# button_circle.net
KiCad netlist of a schematic drawn in EAGLE
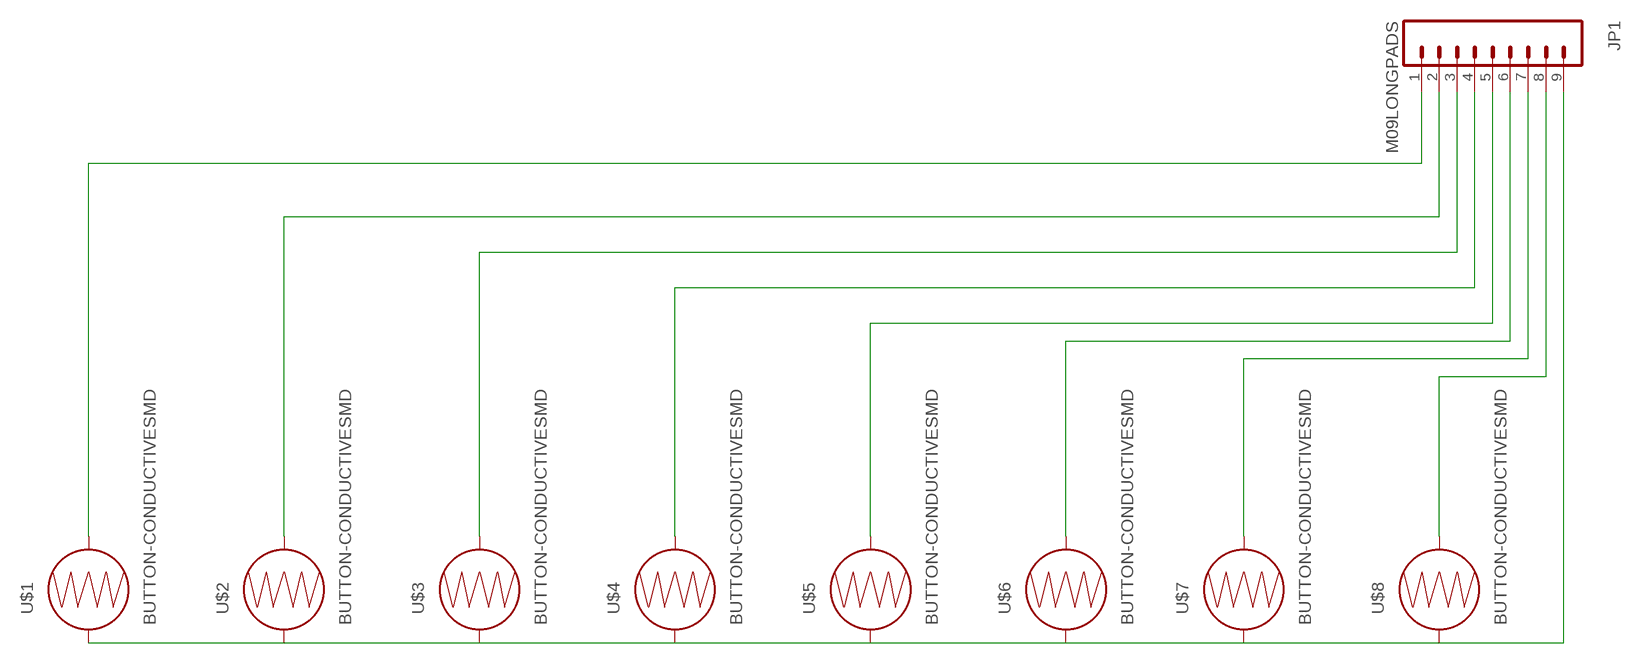
[diagram p0: schematic, sheet 1]

(export (version "E")
  (design (tool "Eeschema 10.0.6"))
  (components
    (comp (ref "JP1")
      (value "M09LONGPADS")
      (footprint "eagle-import:1X09_LONGPADS")
      (libsource (lib "eagle-import") (part "M09LONGPADS"))
    )
    (comp (ref "U$1")
      (value "BUTTON-CONDUCTIVESMD")
      (footprint "eagle-import:BUTTON-CONDUCTIVE")
      (libsource (lib "eagle-import") (part "BUTTON-CONDUCTIVESMD"))
    )
    (comp (ref "U$2")
      (value "BUTTON-CONDUCTIVESMD")
      (footprint "eagle-import:BUTTON-CONDUCTIVE")
      (libsource (lib "eagle-import") (part "BUTTON-CONDUCTIVESMD"))
    )
    (comp (ref "U$3")
      (value "BUTTON-CONDUCTIVESMD")
      (footprint "eagle-import:BUTTON-CONDUCTIVE")
      (libsource (lib "eagle-import") (part "BUTTON-CONDUCTIVESMD"))
    )
    (comp (ref "U$4")
      (value "BUTTON-CONDUCTIVESMD")
      (footprint "eagle-import:BUTTON-CONDUCTIVE")
      (libsource (lib "eagle-import") (part "BUTTON-CONDUCTIVESMD"))
    )
    (comp (ref "U$5")
      (value "BUTTON-CONDUCTIVESMD")
      (footprint "eagle-import:BUTTON-CONDUCTIVE")
      (libsource (lib "eagle-import") (part "BUTTON-CONDUCTIVESMD"))
    )
    (comp (ref "U$6")
      (value "BUTTON-CONDUCTIVESMD")
      (footprint "eagle-import:BUTTON-CONDUCTIVE")
      (libsource (lib "eagle-import") (part "BUTTON-CONDUCTIVESMD"))
    )
    (comp (ref "U$7")
      (value "BUTTON-CONDUCTIVESMD")
      (footprint "eagle-import:BUTTON-CONDUCTIVE")
      (libsource (lib "eagle-import") (part "BUTTON-CONDUCTIVESMD"))
    )
    (comp (ref "U$8")
      (value "BUTTON-CONDUCTIVESMD")
      (footprint "eagle-import:BUTTON-CONDUCTIVE")
      (libsource (lib "eagle-import") (part "BUTTON-CONDUCTIVESMD"))
    )
  )
  (nets
    (net (code "1") (name "Net-(JP1-Pad1)") (class "Default")
      (node (ref "JP1") (pin "1") (pinfunction "1_1") (pintype "passive"))
      (node (ref "U$1") (pin "2") (pinfunction "2_2") (pintype "passive"))
    )
    (net (code "2") (name "Net-(JP1-Pad2)") (class "Default")
      (node (ref "JP1") (pin "2") (pinfunction "2_2") (pintype "passive"))
      (node (ref "U$2") (pin "2") (pinfunction "2_2") (pintype "passive"))
    )
    (net (code "3") (name "Net-(JP1-Pad3)") (class "Default")
      (node (ref "JP1") (pin "3") (pinfunction "3_3") (pintype "passive"))
      (node (ref "U$3") (pin "2") (pinfunction "2_2") (pintype "passive"))
    )
    (net (code "4") (name "Net-(JP1-Pad4)") (class "Default")
      (node (ref "JP1") (pin "4") (pinfunction "4_4") (pintype "passive"))
      (node (ref "U$4") (pin "2") (pinfunction "2_2") (pintype "passive"))
    )
    (net (code "5") (name "Net-(JP1-Pad5)") (class "Default")
      (node (ref "JP1") (pin "5") (pinfunction "5_5") (pintype "passive"))
      (node (ref "U$5") (pin "2") (pinfunction "2_2") (pintype "passive"))
    )
    (net (code "6") (name "Net-(JP1-Pad6)") (class "Default")
      (node (ref "JP1") (pin "6") (pinfunction "6_6") (pintype "passive"))
      (node (ref "U$6") (pin "2") (pinfunction "2_2") (pintype "passive"))
    )
    (net (code "7") (name "Net-(JP1-Pad7)") (class "Default")
      (node (ref "JP1") (pin "7") (pinfunction "7_7") (pintype "passive"))
      (node (ref "U$7") (pin "2") (pinfunction "2_2") (pintype "passive"))
    )
    (net (code "8") (name "Net-(JP1-Pad8)") (class "Default")
      (node (ref "JP1") (pin "8") (pinfunction "8_8") (pintype "passive"))
      (node (ref "U$8") (pin "2") (pinfunction "2_2") (pintype "passive"))
    )
    (net (code "9") (name "Net-(JP1-Pad9)") (class "Default")
      (node (ref "JP1") (pin "9") (pinfunction "9_9") (pintype "passive"))
      (node (ref "U$1") (pin "1") (pinfunction "1_1") (pintype "passive"))
      (node (ref "U$2") (pin "1") (pinfunction "1_1") (pintype "passive"))
      (node (ref "U$3") (pin "1") (pinfunction "1_1") (pintype "passive"))
      (node (ref "U$4") (pin "1") (pinfunction "1_1") (pintype "passive"))
      (node (ref "U$5") (pin "1") (pinfunction "1_1") (pintype "passive"))
      (node (ref "U$7") (pin "1") (pinfunction "1_1") (pintype "passive"))
    )
    (net (code "10") (name "unconnected-(U$6-Pad1)") (class "Default")
      (node (ref "U$6") (pin "1") (pinfunction "1_1") (pintype "passive"))
    )
    (net (code "11") (name "unconnected-(U$8-Pad1)") (class "Default")
      (node (ref "U$8") (pin "1") (pinfunction "1_1") (pintype "passive"))
    )
  )
)
